# SMPS.net
KiCad netlist of a schematic drawn in Altium Designer
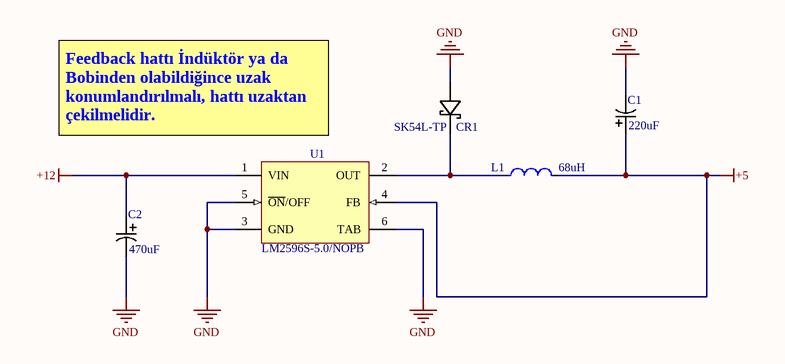
[diagram p0: SMPS.SchDoc]

(export (version "E")
  (design (tool "Eeschema 10.0.6"))
  (components
    (comp (ref "C1")
      (value "220uF")
      (footprint "PCAP_8x10-ELECT_NCA")
      (description "No Description Available")
      (libsource (lib "Integrated_Library_SMPS") (part "UWZ1E221MCL1GS"))
    )
    (comp (ref "C2")
      (value "470uF")
      (footprint "CAPAE1710X1750N")
      (description "470ÂµF 50V Aluminum Electrolytic Capacitors Radial, Can - SMD 80mOhm @ 100kHz 3500 Hrs @ 125Â°C")
      (fields (field (name "MF") "Nichicon") (field (name "MP") "UCZ1H471MNQ1MS"))
      (libsource (lib "Integrated_Library_SMPS") (part "UCZ1H471MNQ1MS"))
    )
    (comp (ref "CR1")
      (value "SK54L-TP")
      (footprint "SDO_SMC-DO-214AB_MCE")
      (description "No Description Available")
      (libsource (lib "Integrated_Library_SMPS") (part "SK54L-TP"))
    )
    (comp (ref "L1")
      (value "68uH")
      (footprint "FP-IHLP-6767GZ-FP_3_825x1-MFG")
      (description "Commercial Inductors, Low DCR Series 68uH 6.1A 75.7mΩ 20%")
      (fields (field (name "TOLERANCE") "20%"))
      (libsource (lib "Integrated_Library_SMPS") (part "CMP-02424-000344-1"))
    )
    (comp (ref "U1")
      (value "LM2596S-5.0/NOPB")
      (footprint "KTT0005B_L")
      (description "SIMPLE SWITCHER® Power Converter 150 KHz 3A Step-Down Voltage Regulator, 5-pin TO-263, Pb-Free")
      (fields (field (name "MANUFACTURER") "Texas Instruments"))
      (libsource (lib "Integrated_Library_SMPS") (part "CMP-0069-00269-3"))
    )
  )
  (nets
    (net (code "1") (name "+5") (class "Default")
      (node (ref "C1") (pin "1") (pinfunction "1_1") (pintype "passive"))
      (node (ref "L1") (pin "2") (pinfunction "2_2") (pintype "passive"))
      (node (ref "U1") (pin "4") (pinfunction "FB_4") (pintype "input"))
    )
    (net (code "2") (name "+12") (class "Default")
      (node (ref "C2") (pin "1") (pinfunction "1_1") (pintype "passive"))
      (node (ref "U1") (pin "1") (pinfunction "VIN_1") (pintype "power_in"))
    )
    (net (code "3") (name "GND") (class "Default")
      (node (ref "C1") (pin "2") (pinfunction "2_2") (pintype "passive"))
      (node (ref "C2") (pin "2") (pinfunction "2_2") (pintype "passive"))
      (node (ref "CR1") (pin "2") (pinfunction "12_2") (pintype "passive"))
      (node (ref "U1") (pin "3") (pinfunction "GND_3") (pintype "power_in"))
      (node (ref "U1") (pin "5") (pinfunction "~{ON}/OFF_5") (pintype "input"))
      (node (ref "U1") (pin "6") (pinfunction "TAB_6") (pintype "power_in"))
    )
    (net (code "4") (name "Net-(CR1-11)") (class "Default")
      (node (ref "CR1") (pin "1") (pinfunction "11_1") (pintype "passive"))
      (node (ref "L1") (pin "1") (pinfunction "1_1") (pintype "passive"))
      (node (ref "U1") (pin "2") (pinfunction "OUT_2") (pintype "power_in"))
    )
  )
)
